# PiOBD_CM4_LTE.net
KiCad netlist of a schematic drawn in Altium Designer
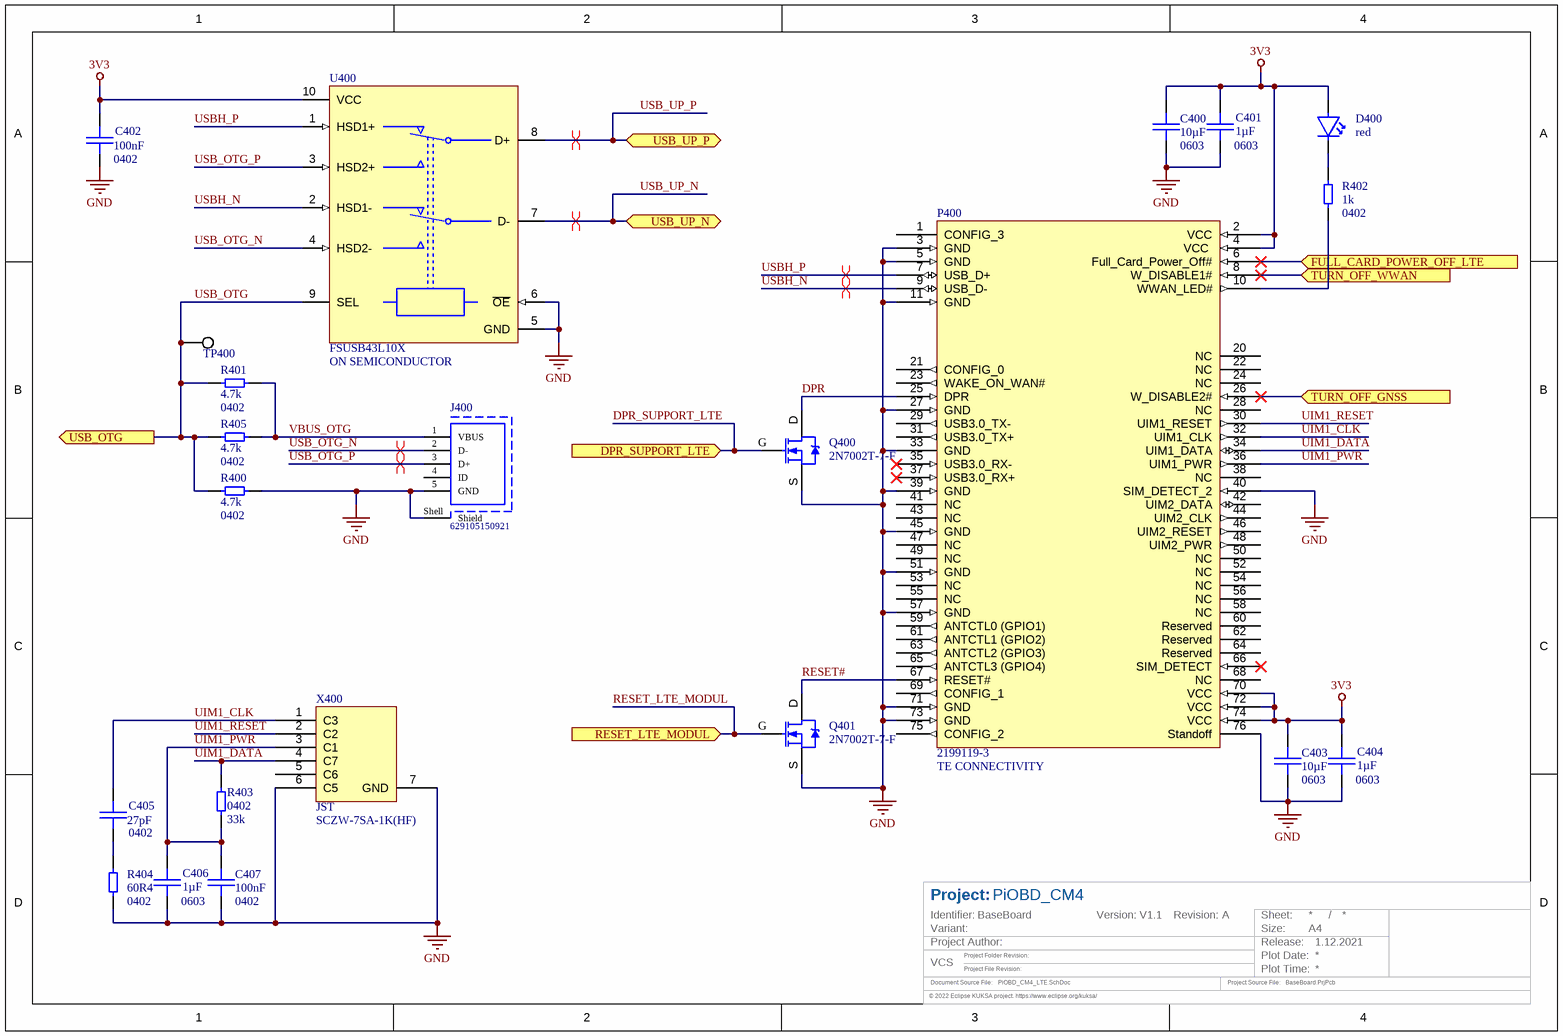
[diagram p0: PiOBD_CM4_LTE.SchDoc]

(export (version "E")
  (design (tool "Eeschema 10.0.6"))
  (components
    (comp (ref "C400")
      (value "CAP 0603 10µF -20% +20% 6.3V X5R")
      (footprint "CAP 0603 [1608 Metric] X080 N")
      (description "SMT 10µF ±20% 6,3 V Keramikkondensatoren X5R")
      (fields
        (field (name "MANUFACTURER PART NUMBER") "GRM188R60J106ME84")
        (field (name "CAPACITANCE") "10µF")
        (field (name "MANUFACTURER") "MURATA")
        (field (name "CASE") "0603")
      )
      (libsource (lib "ShareLib") (part "Capacitor non-polarized - Standard Schematic"))
    )
    (comp (ref "C401")
      (value "CAP 0603 1u -10% +10% 10V X7R")
      (footprint "CAP 0603 [1608 Metric] X080 N")
      (description "SMD/SMT 0603 10V -10% +10% X7R - Multilayer Ceramic Capacitors MLCC")
      (fields
        (field (name "CAPACITANCE") "1µF")
        (field (name "MANUFACTURER PART NUMBER") "GRM188R71A105KA61#")
        (field (name "MANUFACTURER") "MURATA")
        (field (name "CASE") "0603")
      )
      (libsource (lib "ShareLib") (part "Capacitor non-polarized - Standard Schematic"))
    )
    (comp (ref "C402")
      (value "CAP 0402 100n -10% +10% 6.3V X7R")
      (footprint "CAP 0402 [1005 Metric] X050 N")
      (description "SMD/SMT 0402 6.3V -10% +10% X7R - Multilayer Ceramic Capacitors MLCC")
      (fields
        (field (name "MANUFACTURER") "MURATA")
        (field (name "CAPACITANCE") "100nF")
        (field (name "MANUFACTURER PART NUMBER") "GRM155R70J104KA01#")
        (field (name "CASE") "0402")
      )
      (libsource (lib "ShareLib") (part "Capacitor non-polarized - Standard Schematic"))
    )
    (comp (ref "C403")
      (value "CAP 0603 10µF -20% +20% 6.3V X5R")
      (footprint "CAP 0603 [1608 Metric] X080 N")
      (description "SMT 10µF ±20% 6,3 V Keramikkondensatoren X5R")
      (fields
        (field (name "MANUFACTURER PART NUMBER") "GRM188R60J106ME84")
        (field (name "CAPACITANCE") "10µF")
        (field (name "MANUFACTURER") "MURATA")
        (field (name "CASE") "0603")
      )
      (libsource (lib "ShareLib") (part "Capacitor non-polarized - Standard Schematic"))
    )
    (comp (ref "C404")
      (value "CAP 0603 1u -10% +10% 10V X7R")
      (footprint "CAP 0603 [1608 Metric] X080 N")
      (description "SMD/SMT 0603 10V -10% +10% X7R - Multilayer Ceramic Capacitors MLCC")
      (fields
        (field (name "CAPACITANCE") "1µF")
        (field (name "MANUFACTURER PART NUMBER") "GRM188R71A105KA61#")
        (field (name "MANUFACTURER") "MURATA")
        (field (name "CASE") "0603")
      )
      (libsource (lib "ShareLib") (part "Capacitor non-polarized - Standard Schematic"))
    )
    (comp (ref "C405")
      (value "CAP 0402 27p -2% +2% 25V C0G")
      (footprint "CAP 0402 [1005 Metric] X050 N")
      (description "SMD/SMT 0402 25V -2% +2% C0G - Multilayer Ceramic Capacitors MLCC")
      (fields
        (field (name "MANUFACTURER") "MURATA")
        (field (name "CASE") "0402")
        (field (name "MANUFACTURER PART NUMBER") "GRM1555C1E270GA01#")
        (field (name "CAPACITANCE") "27pF")
      )
      (libsource (lib "ShareLib") (part "Capacitor non-polarized - Standard Schematic"))
    )
    (comp (ref "C406")
      (value "CAP 0603 1u -10% +10% 10V X7R")
      (footprint "CAP 0603 [1608 Metric] X080 N")
      (description "SMD/SMT 0603 10V -10% +10% X7R - Multilayer Ceramic Capacitors MLCC")
      (fields
        (field (name "CAPACITANCE") "1µF")
        (field (name "MANUFACTURER PART NUMBER") "GRM188R71A105KA61#")
        (field (name "MANUFACTURER") "MURATA")
        (field (name "CASE") "0603")
      )
      (libsource (lib "ShareLib") (part "Capacitor non-polarized - Standard Schematic"))
    )
    (comp (ref "C407")
      (value "CAP 0402 100n -10% +10% 6.3V X7R")
      (footprint "CAP 0402 [1005 Metric] X050 N")
      (description "SMD/SMT 0402 6.3V -10% +10% X7R - Multilayer Ceramic Capacitors MLCC")
      (fields
        (field (name "MANUFACTURER") "MURATA")
        (field (name "CAPACITANCE") "100nF")
        (field (name "MANUFACTURER PART NUMBER") "GRM155R70J104KA01#")
        (field (name "CASE") "0402")
      )
      (libsource (lib "ShareLib") (part "Capacitor non-polarized - Standard Schematic"))
    )
    (comp (ref "D400")
      (value "WUERTH ELEKTRONIK - 155124RS73200")
      (footprint "WUERTH ELEKTRONIK - WL-SMSW")
      (description "LED, RED, Right Angle SMD 3.2*1.0mm WL-SMSW SMT Mono-color Side view Waterclear")
      (fields
        (field (name "COLOUR LED1") "red")
        (field (name "MANUFACTURER") "WUERTH ELEKTRONIK")
        (field (name "MANUFACTURER PART NUMBER") "155124RS73200")
      )
      (libsource (lib "ShareLib") (part "LED - Standard Schematic"))
    )
    (comp (ref "J400")
      (value "629105150921")
      (footprint "629105150921")
      (description "Micro USB 2.0 Type AB Receptacle WR-COM, Horizontal, SMT")
      (fields (field (name "MANUFACTURER") "Wurth Elektronik") (field (name "PUBLISHER") "WurthElektronik"))
      (libsource (lib "Altium Content Vault") (part "WE-USB-5-1SHLD"))
    )
    (comp (ref "P400")
      (value "TE CONNECTIVITY - 2199119-3")
      (footprint "M.2 (NGFF) Connectors")
      (fields
        (field (name "MANUFACTURER PART NUMBER") "2199119-3")
        (field (name "MANUFACTURER") "TE CONNECTIVITY")
      )
      (libsource (lib "ShareLib") (part "M.2 (NGFF) Connectors"))
    )
    (comp (ref "Q400")
      (value "DIODES INCORPORATED - 2N7002T")
      (footprint "DIODES INCORPORATED - SOT523")
      (description "N-CHANNEL ENHANCEMENT MODE FIELD EFFECT TRANSISTOR")
      (fields
        (field (name "MANUFACTURER") "DIODES INCORPORATED")
        (field (name "MANUFACTURER PART NUMBER") "2N7002T-7-F")
      )
      (libsource (lib "ShareLib") (part "N-Channel, 3-Pin MOSFET, Designator DSG"))
    )
    (comp (ref "Q401")
      (value "DIODES INCORPORATED - 2N7002T")
      (footprint "DIODES INCORPORATED - SOT523")
      (description "N-CHANNEL ENHANCEMENT MODE FIELD EFFECT TRANSISTOR")
      (fields
        (field (name "MANUFACTURER") "DIODES INCORPORATED")
        (field (name "MANUFACTURER PART NUMBER") "2N7002T-7-F")
      )
      (libsource (lib "ShareLib") (part "N-Channel, 3-Pin MOSFET, Designator DSG"))
    )
    (comp (ref "R400")
      (value "RES 0402 4K7 1% 0W0625")
      (footprint "RES 0402 [1005 Metric]_N")
      (description "RC0402 series chip resistor with lead-free terminations made by thick film process")
      (fields
        (field (name "RESISTANCE") "4.7k")
        (field (name "MANUFACTURER PART NUMBER") "RC0402FR-074K7L")
        (field (name "MANUFACTURER") "YAGEO")
        (field (name "CASE") "0402")
      )
      (libsource (lib "ShareLib") (part "Standard Schematic - Resistor Universal"))
    )
    (comp (ref "R401")
      (value "RES 0402 4K7 1% 0W0625")
      (footprint "RES 0402 [1005 Metric]_N")
      (description "RC0402 series chip resistor with lead-free terminations made by thick film process")
      (fields
        (field (name "RESISTANCE") "4.7k")
        (field (name "MANUFACTURER PART NUMBER") "RC0402FR-074K7L")
        (field (name "MANUFACTURER") "YAGEO")
        (field (name "CASE") "0402")
      )
      (libsource (lib "ShareLib") (part "Standard Schematic - Resistor Universal"))
    )
    (comp (ref "R402")
      (value "RES 0402 1K 1% 0W0625")
      (footprint "RES 0402 [1005 Metric]_N")
      (description "RC0402 series chip resistor with lead-free terminations made by thick film process")
      (fields
        (field (name "CASE") "0402")
        (field (name "MANUFACTURER PART NUMBER") "RC0402FR-071KL")
        (field (name "MANUFACTURER") "YAGEO")
        (field (name "RESISTANCE") "1k")
      )
      (libsource (lib "ShareLib") (part "Standard Schematic - Resistor Universal"))
    )
    (comp (ref "R403")
      (value "RES 0402 33K 1% 0W0625")
      (footprint "RES 0402 [1005 Metric]_N")
      (description "RC0402 series chip resistor with lead-free terminations made by thick film process")
      (fields
        (field (name "MANUFACTURER") "YAGEO")
        (field (name "CASE") "0402")
        (field (name "MANUFACTURER PART NUMBER") "RC0402FR-0733KL")
        (field (name "RESISTANCE") "33k")
      )
      (libsource (lib "ShareLib") (part "Standard Schematic - Resistor Universal"))
    )
    (comp (ref "R404")
      (value "RES 0402 60R4 1% 0W0625")
      (footprint "RES 0402 [1005 Metric]_N")
      (description "RC0402 series chip resistor with lead-free terminations made by thick film process")
      (fields
        (field (name "RESISTANCE") "60R4")
        (field (name "MANUFACTURER PART NUMBER") "RC0402FR-0760R4L")
        (field (name "MANUFACTURER") "YAGEO")
        (field (name "CASE") "0402")
      )
      (libsource (lib "ShareLib") (part "Standard Schematic - Resistor Universal"))
    )
    (comp (ref "R405")
      (value "RES 0402 4K7 1% 0W0625")
      (footprint "RES 0402 [1005 Metric]_N")
      (description "RC0402 series chip resistor with lead-free terminations made by thick film process")
      (fields
        (field (name "RESISTANCE") "4.7k")
        (field (name "MANUFACTURER PART NUMBER") "RC0402FR-074K7L")
        (field (name "MANUFACTURER") "YAGEO")
        (field (name "CASE") "0402")
      )
      (libsource (lib "ShareLib") (part "Standard Schematic - Resistor Universal"))
    )
    (comp (ref "TP400")
      (value "Testpad, 0.8mm x 0.8mm, round")
      (footprint "Testpad, 0.8mm x 0.8mm, round")
      (libsource (lib "ShareLib") (part "Testpoint (No BOM)"))
    )
    (comp (ref "U400")
      (value "ON SEMICONDUCTOR - FSUSB43L10X")
      (footprint "ON SEMICONDUCTOR - FSUSB43L10X")
      (description "Low-Power, Two-Port, High-Speed, USB2.0 (480Mbps) Switch")
      (fields
        (field (name "MANUFACTURER PART NUMBER") "FSUSB43L10X")
        (field (name "MANUFACTURER") "ON SEMICONDUCTOR")
      )
      (libsource (lib "ShareLib") (part "ON SEMICONDUCTOR - FSUSB43L10X"))
    )
    (comp (ref "X400")
      (value "JST - SCZW-7SA-1K(HF)")
      (footprint "JST SCZW-7SA-1K(HF)")
      (description "SIM-Kartenleser aufklappbar und sperrfähig")
      (fields (field (name "MANUFACTURER") "JST") (field (name "MANUFACTURER PART NUMBER") "SCZW-7SA-1K(HF)"))
      (libsource (lib "ShareLib") (part "JST SCZW-7SA-1K(HF)"))
    )
  )
  (nets
    (net (code "1") (name "/DPR") (class "Default")
      (node (ref "P400") (pin "25") (pinfunction "DPR_25") (pintype "input"))
      (node (ref "Q400") (pin "D") (pinfunction "D_D") (pintype "passive"))
    )
    (net (code "2") (name "/DPR_SUPPORT_LTE") (class "Default")
      (node (ref "Q400") (pin "G") (pinfunction "G_G") (pintype "passive"))
    )
    (net (code "3") (name "/FULL_CARD_POWER_OFF_LTE") (class "Default")
      (node (ref "P400") (pin "6") (pinfunction "Full_Card_Power_Off#_6") (pintype "input+no_connect"))
    )
    (net (code "4") (name "/RESET#") (class "Default")
      (node (ref "P400") (pin "67") (pinfunction "RESET#_67") (pintype "input"))
      (node (ref "Q401") (pin "D") (pinfunction "D_D") (pintype "passive"))
    )
    (net (code "5") (name "/RESET_LTE_MODUL") (class "Default")
      (node (ref "Q401") (pin "G") (pinfunction "G_G") (pintype "passive"))
    )
    (net (code "6") (name "/TURN_OFF_GNSS") (class "Default")
      (node (ref "P400") (pin "26") (pinfunction "W_DISABLE2#_26") (pintype "input+no_connect"))
    )
    (net (code "7") (name "/TURN_OFF_WWAN") (class "Default")
      (node (ref "P400") (pin "8") (pinfunction "W_DISABLE1#_8") (pintype "input+no_connect"))
    )
    (net (code "8") (name "/UIM1_CLK") (class "Default")
      (node (ref "C405") (pin "2") (pinfunction "2_2") (pintype "passive"))
      (node (ref "P400") (pin "32") (pinfunction "UIM1_CLK_32") (pintype "output"))
      (node (ref "X400") (pin "1") (pinfunction "C3_1") (pintype "passive"))
    )
    (net (code "9") (name "/UIM1_DATA") (class "Default")
      (node (ref "P400") (pin "34") (pinfunction "UIM1_DATA_34") (pintype "bidirectional"))
      (node (ref "R403") (pin "1") (pinfunction "1_1") (pintype "passive"))
      (node (ref "X400") (pin "4") (pinfunction "C7_4") (pintype "passive"))
    )
    (net (code "10") (name "/UIM1_PWR") (class "Default")
      (node (ref "C406") (pin "1") (pinfunction "1_1") (pintype "passive"))
      (node (ref "C407") (pin "1") (pinfunction "1_1") (pintype "passive"))
      (node (ref "P400") (pin "36") (pinfunction "UIM1_PWR_36") (pintype "output"))
      (node (ref "R403") (pin "2") (pinfunction "2_2") (pintype "passive"))
      (node (ref "X400") (pin "3") (pinfunction "C1_3") (pintype "passive"))
    )
    (net (code "11") (name "/UIM1_RESET") (class "Default")
      (node (ref "P400") (pin "30") (pinfunction "UIM1_RESET_30") (pintype "output"))
      (node (ref "X400") (pin "2") (pinfunction "C2_2") (pintype "passive"))
    )
    (net (code "12") (name "/USBH_N") (class "Default")
      (node (ref "P400") (pin "9") (pinfunction "USB_D-_9") (pintype "bidirectional"))
      (node (ref "U400") (pin "2") (pinfunction "HSD1-_2") (pintype "input"))
    )
    (net (code "13") (name "/USBH_P") (class "Default")
      (node (ref "P400") (pin "7") (pinfunction "USB_D+_7") (pintype "bidirectional"))
      (node (ref "U400") (pin "1") (pinfunction "HSD1+_1") (pintype "input"))
    )
    (net (code "14") (name "/USB_OTG") (class "Default")
      (node (ref "R400") (pin "2") (pinfunction "2_2") (pintype "passive"))
      (node (ref "R401") (pin "2") (pinfunction "2_2") (pintype "passive"))
      (node (ref "R405") (pin "2") (pinfunction "2_2") (pintype "passive"))
      (node (ref "TP400") (pin "1") (pinfunction "1_1") (pintype "passive"))
      (node (ref "U400") (pin "9") (pinfunction "SEL_9") (pintype "passive"))
    )
    (net (code "15") (name "/USB_OTG_N") (class "Default")
      (node (ref "J400") (pin "2") (pinfunction "D-_2") (pintype "passive"))
      (node (ref "U400") (pin "4") (pinfunction "HSD2-_4") (pintype "input"))
    )
    (net (code "16") (name "/USB_OTG_P") (class "Default")
      (node (ref "J400") (pin "3") (pinfunction "D+_3") (pintype "passive"))
      (node (ref "U400") (pin "3") (pinfunction "HSD2+_3") (pintype "input"))
    )
    (net (code "17") (name "/USB_UP_N") (class "Default")
      (node (ref "U400") (pin "7") (pinfunction "D-_7") (pintype "passive"))
    )
    (net (code "18") (name "/USB_UP_P") (class "Default")
      (node (ref "U400") (pin "8") (pinfunction "D+_8") (pintype "passive"))
    )
    (net (code "19") (name "/VBUS_OTG") (class "Default")
      (node (ref "J400") (pin "1") (pinfunction "VBUS_1") (pintype "passive"))
      (node (ref "R401") (pin "1") (pinfunction "1_1") (pintype "passive"))
      (node (ref "R405") (pin "1") (pinfunction "1_1") (pintype "passive"))
    )
    (net (code "20") (name "3V3") (class "Default")
      (node (ref "C400") (pin "1") (pinfunction "1_1") (pintype "passive"))
      (node (ref "C401") (pin "1") (pinfunction "1_1") (pintype "passive"))
      (node (ref "C402") (pin "2") (pinfunction "2_2") (pintype "passive"))
      (node (ref "C403") (pin "1") (pinfunction "1_1") (pintype "passive"))
      (node (ref "C404") (pin "1") (pinfunction "1_1") (pintype "passive"))
      (node (ref "D400") (pin "A") (pinfunction "A_A") (pintype "passive"))
      (node (ref "P400") (pin "2") (pinfunction "VCC_2") (pintype "input"))
      (node (ref "P400") (pin "4") (pinfunction "VCC_4") (pintype "input"))
      (node (ref "P400") (pin "70") (pinfunction "VCC_70") (pintype "input"))
      (node (ref "P400") (pin "72") (pinfunction "VCC_72") (pintype "input"))
      (node (ref "P400") (pin "74") (pinfunction "VCC_74") (pintype "input"))
      (node (ref "U400") (pin "10") (pinfunction "VCC_10") (pintype "power_in"))
    )
    (net (code "21") (name "GND") (class "Default")
      (node (ref "C400") (pin "2") (pinfunction "2_2") (pintype "passive"))
      (node (ref "C401") (pin "2") (pinfunction "2_2") (pintype "passive"))
      (node (ref "C402") (pin "1") (pinfunction "1_1") (pintype "passive"))
      (node (ref "C403") (pin "2") (pinfunction "2_2") (pintype "passive"))
      (node (ref "C404") (pin "2") (pinfunction "2_2") (pintype "passive"))
      (node (ref "C406") (pin "2") (pinfunction "2_2") (pintype "passive"))
      (node (ref "C407") (pin "2") (pinfunction "2_2") (pintype "passive"))
      (node (ref "J400") (pin "5") (pinfunction "GND_5") (pintype "passive"))
      (node (ref "J400") (pin "Shell") (pinfunction "Shield_Shell") (pintype "passive"))
      (node (ref "P400") (pin "11") (pinfunction "GND_11") (pintype "input"))
      (node (ref "P400") (pin "27") (pinfunction "GND_27") (pintype "input"))
      (node (ref "P400") (pin "3") (pinfunction "GND_3") (pintype "input"))
      (node (ref "P400") (pin "33") (pinfunction "GND_33") (pintype "passive"))
      (node (ref "P400") (pin "39") (pinfunction "GND_39") (pintype "input"))
      (node (ref "P400") (pin "40") (pinfunction "SIM_DETECT_2_40") (pintype "input"))
      (node (ref "P400") (pin "45") (pinfunction "GND_45") (pintype "input"))
      (node (ref "P400") (pin "5") (pinfunction "GND_5") (pintype "input"))
      (node (ref "P400") (pin "51") (pinfunction "GND_51") (pintype "input"))
      (node (ref "P400") (pin "57") (pinfunction "GND_57") (pintype "input"))
      (node (ref "P400") (pin "71") (pinfunction "GND_71") (pintype "input"))
      (node (ref "P400") (pin "73") (pinfunction "GND_73") (pintype "input"))
      (node (ref "P400") (pin "76") (pinfunction "Standoff_76") (pintype "passive"))
      (node (ref "Q400") (pin "S") (pinfunction "S_S") (pintype "passive"))
      (node (ref "Q401") (pin "S") (pinfunction "S_S") (pintype "passive"))
      (node (ref "R400") (pin "1") (pinfunction "1_1") (pintype "passive"))
      (node (ref "R404") (pin "1") (pinfunction "1_1") (pintype "passive"))
      (node (ref "U400") (pin "5") (pinfunction "GND_5") (pintype "power_in"))
      (node (ref "U400") (pin "6") (pinfunction "~{OE}_6") (pintype "input"))
      (node (ref "X400") (pin "6") (pinfunction "C5_6") (pintype "passive"))
      (node (ref "X400") (pin "7") (pinfunction "GND_7") (pintype "passive"))
    )
    (net (code "22") (name "Net-(C405-Pad1)") (class "Default")
      (node (ref "C405") (pin "1") (pinfunction "1_1") (pintype "passive"))
      (node (ref "R404") (pin "2") (pinfunction "2_2") (pintype "passive"))
    )
    (net (code "23") (name "Net-(D400-PadC)") (class "Default")
      (node (ref "D400") (pin "C") (pinfunction "C_C") (pintype "passive"))
      (node (ref "R402") (pin "2") (pinfunction "2_2") (pintype "passive"))
    )
    (net (code "24") (name "Net-(P400-WWAN_LED#)") (class "Default")
      (node (ref "P400") (pin "10") (pinfunction "WWAN_LED#_10") (pintype "output"))
      (node (ref "R402") (pin "1") (pinfunction "1_1") (pintype "passive"))
    )
    (net (code "25") (name "unconnected-(J400-ID-Pad4)") (class "Default")
      (node (ref "J400") (pin "4") (pinfunction "ID_4") (pintype "passive"))
    )
    (net (code "26") (name "unconnected-(P400-ANTCTL0_(GPIO1)-Pad59)") (class "Default")
      (node (ref "P400") (pin "59") (pinfunction "ANTCTL0_(GPIO1)_59") (pintype "output"))
    )
    (net (code "27") (name "unconnected-(P400-ANTCTL1_(GPIO2)-Pad61)") (class "Default")
      (node (ref "P400") (pin "61") (pinfunction "ANTCTL1_(GPIO2)_61") (pintype "output"))
    )
    (net (code "28") (name "unconnected-(P400-ANTCTL2_(GPIO3)-Pad63)") (class "Default")
      (node (ref "P400") (pin "63") (pinfunction "ANTCTL2_(GPIO3)_63") (pintype "output"))
    )
    (net (code "29") (name "unconnected-(P400-ANTCTL3_(GPIO4)-Pad65)") (class "Default")
      (node (ref "P400") (pin "65") (pinfunction "ANTCTL3_(GPIO4)_65") (pintype "output"))
    )
    (net (code "30") (name "unconnected-(P400-CONFIG_0-Pad21)") (class "Default")
      (node (ref "P400") (pin "21") (pinfunction "CONFIG_0_21") (pintype "output"))
    )
    (net (code "31") (name "unconnected-(P400-CONFIG_1-Pad69)") (class "Default")
      (node (ref "P400") (pin "69") (pinfunction "CONFIG_1_69") (pintype "output"))
    )
    (net (code "32") (name "unconnected-(P400-CONFIG_2-Pad75)") (class "Default")
      (node (ref "P400") (pin "75") (pinfunction "CONFIG_2_75") (pintype "output"))
    )
    (net (code "33") (name "unconnected-(P400-CONFIG_3-Pad1)") (class "Default")
      (node (ref "P400") (pin "1") (pinfunction "CONFIG_3_1") (pintype "passive"))
    )
    (net (code "34") (name "unconnected-(P400-NC-Pad20)") (class "Default")
      (node (ref "P400") (pin "20") (pinfunction "NC_20") (pintype "passive"))
    )
    (net (code "35") (name "unconnected-(P400-NC-Pad22)") (class "Default")
      (node (ref "P400") (pin "22") (pinfunction "NC_22") (pintype "passive"))
    )
    (net (code "36") (name "unconnected-(P400-NC-Pad24)") (class "Default")
      (node (ref "P400") (pin "24") (pinfunction "NC_24") (pintype "passive"))
    )
    (net (code "37") (name "unconnected-(P400-NC-Pad28)") (class "Default")
      (node (ref "P400") (pin "28") (pinfunction "NC_28") (pintype "passive"))
    )
    (net (code "38") (name "unconnected-(P400-NC-Pad38)") (class "Default")
      (node (ref "P400") (pin "38") (pinfunction "NC_38") (pintype "passive"))
    )
    (net (code "39") (name "unconnected-(P400-NC-Pad41)") (class "Default")
      (node (ref "P400") (pin "41") (pinfunction "NC_41") (pintype "passive"))
    )
    (net (code "40") (name "unconnected-(P400-NC-Pad43)") (class "Default")
      (node (ref "P400") (pin "43") (pinfunction "NC_43") (pintype "passive"))
    )
    (net (code "41") (name "unconnected-(P400-NC-Pad47)") (class "Default")
      (node (ref "P400") (pin "47") (pinfunction "NC_47") (pintype "passive"))
    )
    (net (code "42") (name "unconnected-(P400-NC-Pad49)") (class "Default")
      (node (ref "P400") (pin "49") (pinfunction "NC_49") (pintype "passive"))
    )
    (net (code "43") (name "unconnected-(P400-NC-Pad50)") (class "Default")
      (node (ref "P400") (pin "50") (pinfunction "NC_50") (pintype "passive"))
    )
    (net (code "44") (name "unconnected-(P400-NC-Pad52)") (class "Default")
      (node (ref "P400") (pin "52") (pinfunction "NC_52") (pintype "passive"))
    )
    (net (code "45") (name "unconnected-(P400-NC-Pad53)") (class "Default")
      (node (ref "P400") (pin "53") (pinfunction "NC_53") (pintype "passive"))
    )
    (net (code "46") (name "unconnected-(P400-NC-Pad54)") (class "Default")
      (node (ref "P400") (pin "54") (pinfunction "NC_54") (pintype "passive"))
    )
    (net (code "47") (name "unconnected-(P400-NC-Pad55)") (class "Default")
      (node (ref "P400") (pin "55") (pinfunction "NC_55") (pintype "passive"))
    )
    (net (code "48") (name "unconnected-(P400-NC-Pad56)") (class "Default")
      (node (ref "P400") (pin "56") (pinfunction "NC_56") (pintype "passive"))
    )
    (net (code "49") (name "unconnected-(P400-NC-Pad58)") (class "Default")
      (node (ref "P400") (pin "58") (pinfunction "NC_58") (pintype "passive"))
    )
    (net (code "50") (name "unconnected-(P400-NC-Pad68)") (class "Default")
      (node (ref "P400") (pin "68") (pinfunction "NC_68") (pintype "passive"))
    )
    (net (code "51") (name "unconnected-(P400-Reserved-Pad60)") (class "Default")
      (node (ref "P400") (pin "60") (pinfunction "Reserved_60") (pintype "passive"))
    )
    (net (code "52") (name "unconnected-(P400-Reserved-Pad62)") (class "Default")
      (node (ref "P400") (pin "62") (pinfunction "Reserved_62") (pintype "passive"))
    )
    (net (code "53") (name "unconnected-(P400-Reserved-Pad64)") (class "Default")
      (node (ref "P400") (pin "64") (pinfunction "Reserved_64") (pintype "passive"))
    )
    (net (code "54") (name "unconnected-(P400-SIM_DETECT-Pad66)") (class "Default")
      (node (ref "P400") (pin "66") (pinfunction "SIM_DETECT_66") (pintype "input+no_connect"))
    )
    (net (code "55") (name "unconnected-(P400-UIM2_CLK-Pad44)") (class "Default")
      (node (ref "P400") (pin "44") (pinfunction "UIM2_CLK_44") (pintype "output"))
    )
    (net (code "56") (name "unconnected-(P400-UIM2_DATA-Pad42)") (class "Default")
      (node (ref "P400") (pin "42") (pinfunction "UIM2_DATA_42") (pintype "bidirectional"))
    )
    (net (code "57") (name "unconnected-(P400-UIM2_PWR-Pad48)") (class "Default")
      (node (ref "P400") (pin "48") (pinfunction "UIM2_PWR_48") (pintype "output"))
    )
    (net (code "58") (name "unconnected-(P400-UIM2_RESET-Pad46)") (class "Default")
      (node (ref "P400") (pin "46") (pinfunction "UIM2_RESET_46") (pintype "output"))
    )
    (net (code "59") (name "unconnected-(P400-USB3.0_RX+-Pad37)") (class "Default")
      (node (ref "P400") (pin "37") (pinfunction "USB3.0_RX+_37") (pintype "input+no_connect"))
    )
    (net (code "60") (name "unconnected-(P400-USB3.0_RX--Pad35)") (class "Default")
      (node (ref "P400") (pin "35") (pinfunction "USB3.0_RX-_35") (pintype "input+no_connect"))
    )
    (net (code "61") (name "unconnected-(P400-USB3.0_TX+-Pad31)") (class "Default")
      (node (ref "P400") (pin "31") (pinfunction "USB3.0_TX+_31") (pintype "output"))
    )
    (net (code "62") (name "unconnected-(P400-USB3.0_TX--Pad29)") (class "Default")
      (node (ref "P400") (pin "29") (pinfunction "USB3.0_TX-_29") (pintype "output"))
    )
    (net (code "63") (name "unconnected-(P400-WAKE_ON_WAN#-Pad23)") (class "Default")
      (node (ref "P400") (pin "23") (pinfunction "WAKE_ON_WAN#_23") (pintype "output"))
    )
    (net (code "64") (name "unconnected-(X400-C6-Pad5)") (class "Default")
      (node (ref "X400") (pin "5") (pinfunction "C6_5") (pintype "passive"))
    )
  )
)
